# killbox.net
KiCad netlist of a schematic drawn in EAGLE
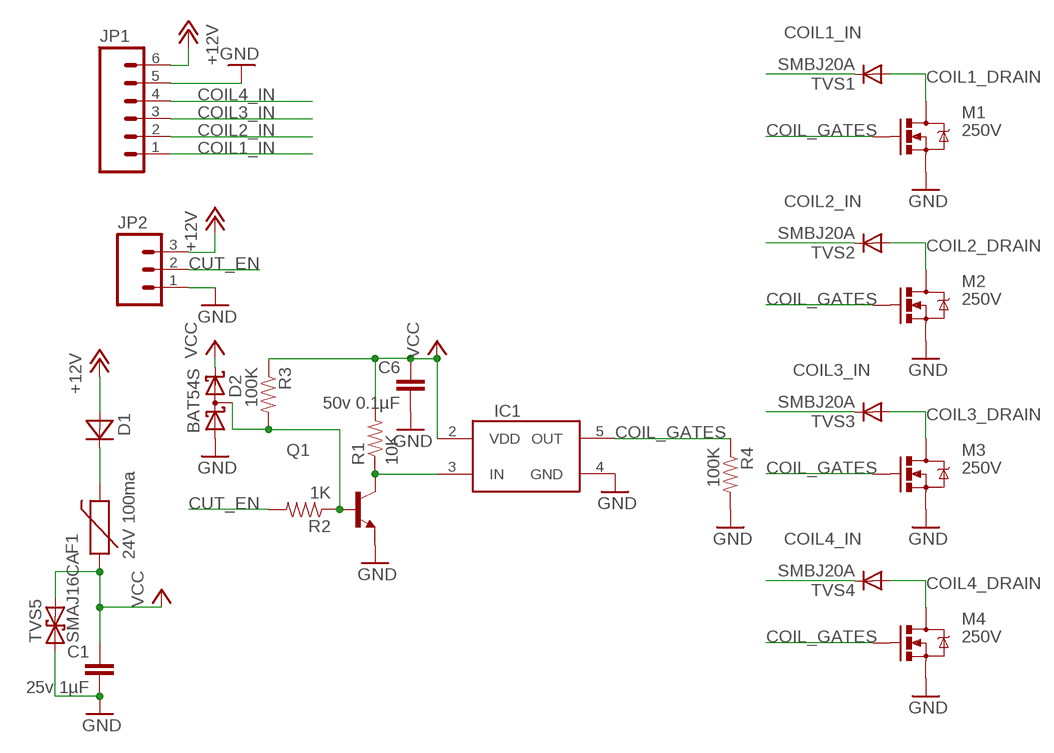
[diagram p0: schematic, sheet 1]

(export (version "E")
  (design (tool "Eeschema 10.0.6"))
  (components
    (comp (ref "C1")
      (value "25v 1µF")
      (footprint "eagle-import:0603-CAP")
      (libsource (lib "eagle-import") (part "CAP0603-CAP"))
    )
    (comp (ref "C6")
      (value "50v 0.1µF")
      (footprint "eagle-import:0603-CAP")
      (libsource (lib "eagle-import") (part "CAP0603-CAP"))
    )
    (comp (ref "D1")
      (value "MBRA340T3")
      (footprint "eagle-import:SMA")
      (libsource (lib "eagle-import") (part "MBRA340T3"))
    )
    (comp (ref "D2")
      (value "BAT54S")
      (footprint "eagle-import:SOT23")
      (libsource (lib "eagle-import") (part "BAT54S"))
    )
    (comp (ref "F1")
      (value "24V 100ma")
      (footprint "eagle-import:PTC-1206")
      (libsource (lib "eagle-import") (part "PTCSMD"))
    )
    (comp (ref "IC1")
      (value "MCP1416")
      (footprint "eagle-import:SOT23-5")
      (libsource (lib "eagle-import") (part "MCP1416"))
    )
    (comp (ref "JP1")
      (value "M063.5MM-6")
      (footprint "eagle-import:SCREWTERMINAL-3.5MM-6")
      (libsource (lib "eagle-import") (part "M063.5MM-6"))
    )
    (comp (ref "JP2")
      (value "M03-SCREW-5MM")
      (footprint "eagle-import:SCREWTERMINAL-5MM-3")
      (libsource (lib "eagle-import") (part "M03-SCREW-5MM"))
    )
    (comp (ref "M1")
      (value "250V")
      (footprint "eagle-import:DPAK")
      (libsource (lib "eagle-import") (part "MOSFET-NCHANNELFDD8780"))
    )
    (comp (ref "M2")
      (value "250V")
      (footprint "eagle-import:DPAK")
      (libsource (lib "eagle-import") (part "MOSFET-NCHANNELFDD8780"))
    )
    (comp (ref "M3")
      (value "250V")
      (footprint "eagle-import:DPAK")
      (libsource (lib "eagle-import") (part "MOSFET-NCHANNELFDD8780"))
    )
    (comp (ref "M4")
      (value "250V")
      (footprint "eagle-import:DPAK")
      (libsource (lib "eagle-import") (part "MOSFET-NCHANNELFDD8780"))
    )
    (comp (ref "Q1")
      (value "MMBT2222ALT1-NPN-SOT23-BEC")
      (footprint "eagle-import:SOT23-BEC")
      (libsource (lib "eagle-import") (part "-NPN-SOT23-BECMMBT2222ALT1"))
    )
    (comp (ref "R1")
      (value "10K")
      (footprint "eagle-import:0603-RES")
      (libsource (lib "eagle-import") (part "RESISTOR0603-RES"))
    )
    (comp (ref "R2")
      (value "1K")
      (footprint "eagle-import:0603-RES")
      (libsource (lib "eagle-import") (part "RESISTOR0603-RES"))
    )
    (comp (ref "R3")
      (value "100K")
      (footprint "eagle-import:0603-RES")
      (libsource (lib "eagle-import") (part "RESISTOR0603-RES"))
    )
    (comp (ref "R4")
      (value "100K")
      (footprint "eagle-import:0603-RES")
      (libsource (lib "eagle-import") (part "RESISTOR0603-RES"))
    )
    (comp (ref "TVS1")
      (value "SMBJ20A")
      (footprint "eagle-import:SMB-DIODE")
      (libsource (lib "eagle-import") (part "DIODESMB"))
    )
    (comp (ref "TVS2")
      (value "SMBJ20A")
      (footprint "eagle-import:SMB-DIODE")
      (libsource (lib "eagle-import") (part "DIODESMB"))
    )
    (comp (ref "TVS3")
      (value "SMBJ20A")
      (footprint "eagle-import:SMB-DIODE")
      (libsource (lib "eagle-import") (part "DIODESMB"))
    )
    (comp (ref "TVS4")
      (value "SMBJ20A")
      (footprint "eagle-import:SMB-DIODE")
      (libsource (lib "eagle-import") (part "DIODESMB"))
    )
    (comp (ref "TVS5")
      (value "SMAJ16CA")
      (footprint "eagle-import:SMA-DIODE")
      (libsource (lib "eagle-import") (part "TVS"))
    )
  )
  (nets
    (net (code "1") (name "+12V") (class "Default")
      (node (ref "D1") (pin "A") (pinfunction "A_A") (pintype "passive"))
      (node (ref "JP1") (pin "6") (pinfunction "6_6") (pintype "passive"))
      (node (ref "JP2") (pin "3") (pinfunction "3_3") (pintype "passive"))
    )
    (net (code "2") (name "/COIL1_DRAIN") (class "Default")
      (node (ref "M1") (pin "4") (pinfunction "D_4") (pintype "passive"))
      (node (ref "TVS1") (pin "A") (pinfunction "A_A") (pintype "passive"))
    )
    (net (code "3") (name "/COIL1_IN") (class "Default")
      (node (ref "JP1") (pin "1") (pinfunction "1_1") (pintype "passive"))
      (node (ref "TVS1") (pin "C") (pinfunction "C_C") (pintype "passive"))
    )
    (net (code "4") (name "/COIL2_DRAIN") (class "Default")
      (node (ref "M2") (pin "4") (pinfunction "D_4") (pintype "passive"))
      (node (ref "TVS2") (pin "A") (pinfunction "A_A") (pintype "passive"))
    )
    (net (code "5") (name "/COIL2_IN") (class "Default")
      (node (ref "JP1") (pin "2") (pinfunction "2_2") (pintype "passive"))
      (node (ref "TVS2") (pin "C") (pinfunction "C_C") (pintype "passive"))
    )
    (net (code "6") (name "/COIL3_DRAIN") (class "Default")
      (node (ref "M3") (pin "4") (pinfunction "D_4") (pintype "passive"))
      (node (ref "TVS3") (pin "A") (pinfunction "A_A") (pintype "passive"))
    )
    (net (code "7") (name "/COIL3_IN") (class "Default")
      (node (ref "JP1") (pin "3") (pinfunction "3_3") (pintype "passive"))
      (node (ref "TVS3") (pin "C") (pinfunction "C_C") (pintype "passive"))
    )
    (net (code "8") (name "/COIL4_DRAIN") (class "Default")
      (node (ref "M4") (pin "4") (pinfunction "D_4") (pintype "passive"))
      (node (ref "TVS4") (pin "A") (pinfunction "A_A") (pintype "passive"))
    )
    (net (code "9") (name "/COIL4_IN") (class "Default")
      (node (ref "JP1") (pin "4") (pinfunction "4_4") (pintype "passive"))
      (node (ref "TVS4") (pin "C") (pinfunction "C_C") (pintype "passive"))
    )
    (net (code "10") (name "/COIL_GATES") (class "Default")
      (node (ref "IC1") (pin "5") (pinfunction "OUT_5") (pintype "bidirectional"))
      (node (ref "M1") (pin "1") (pinfunction "G_1") (pintype "passive"))
      (node (ref "M2") (pin "1") (pinfunction "G_1") (pintype "passive"))
      (node (ref "M3") (pin "1") (pinfunction "G_1") (pintype "passive"))
      (node (ref "M4") (pin "1") (pinfunction "G_1") (pintype "passive"))
      (node (ref "R4") (pin "1") (pinfunction "1_1") (pintype "passive"))
    )
    (net (code "11") (name "/CUT_EN") (class "Default")
      (node (ref "JP2") (pin "2") (pinfunction "2_2") (pintype "passive"))
      (node (ref "R2") (pin "2") (pinfunction "2_2") (pintype "passive"))
    )
    (net (code "12") (name "GND") (class "Default")
      (node (ref "C1") (pin "2") (pinfunction "2_2") (pintype "passive"))
      (node (ref "C6") (pin "2") (pinfunction "2_2") (pintype "passive"))
      (node (ref "D2") (pin "1") (pinfunction "A1_1") (pintype "passive"))
      (node (ref "IC1") (pin "4") (pinfunction "GND_4") (pintype "bidirectional"))
      (node (ref "JP1") (pin "5") (pinfunction "5_5") (pintype "passive"))
      (node (ref "JP2") (pin "1") (pinfunction "1_1") (pintype "passive"))
      (node (ref "M1") (pin "3") (pinfunction "S_3") (pintype "passive"))
      (node (ref "M2") (pin "3") (pinfunction "S_3") (pintype "passive"))
      (node (ref "M3") (pin "3") (pinfunction "S_3") (pintype "passive"))
      (node (ref "M4") (pin "3") (pinfunction "S_3") (pintype "passive"))
      (node (ref "Q1") (pin "E") (pinfunction "E_E") (pintype "passive"))
      (node (ref "R4") (pin "2") (pinfunction "2_2") (pintype "passive"))
      (node (ref "TVS5") (pin "A") (pinfunction "1_A") (pintype "passive"))
    )
    (net (code "13") (name "Net-(D1-PadC)") (class "Default")
      (node (ref "D1") (pin "C") (pinfunction "C_C") (pintype "passive"))
      (node (ref "F1") (pin "2") (pinfunction "2_2") (pintype "bidirectional"))
    )
    (net (code "14") (name "Net-(D2-C1A2)") (class "Default")
      (node (ref "D2") (pin "3") (pinfunction "C1A2_3") (pintype "passive"))
      (node (ref "Q1") (pin "B") (pinfunction "B_B") (pintype "passive"))
      (node (ref "R2") (pin "1") (pinfunction "1_1") (pintype "passive"))
      (node (ref "R3") (pin "2") (pinfunction "2_2") (pintype "passive"))
    )
    (net (code "15") (name "Net-(IC1-IN)") (class "Default")
      (node (ref "IC1") (pin "3") (pinfunction "IN_3") (pintype "bidirectional"))
      (node (ref "Q1") (pin "C") (pinfunction "C_C") (pintype "passive"))
      (node (ref "R1") (pin "1") (pinfunction "1_1") (pintype "passive"))
    )
    (net (code "16") (name "VCC") (class "Default")
      (node (ref "C1") (pin "1") (pinfunction "1_1") (pintype "passive"))
      (node (ref "C6") (pin "1") (pinfunction "1_1") (pintype "passive"))
      (node (ref "D2") (pin "2") (pinfunction "C2_2") (pintype "passive"))
      (node (ref "F1") (pin "1") (pinfunction "1_1") (pintype "bidirectional"))
      (node (ref "IC1") (pin "2") (pinfunction "VDD_2") (pintype "bidirectional"))
      (node (ref "R1") (pin "2") (pinfunction "2_2") (pintype "passive"))
      (node (ref "R3") (pin "1") (pinfunction "1_1") (pintype "passive"))
      (node (ref "TVS5") (pin "C") (pinfunction "2_C") (pintype "passive"))
    )
  )
)
